# placa_servo2.net
KiCad netlist of a schematic drawn in EAGLE
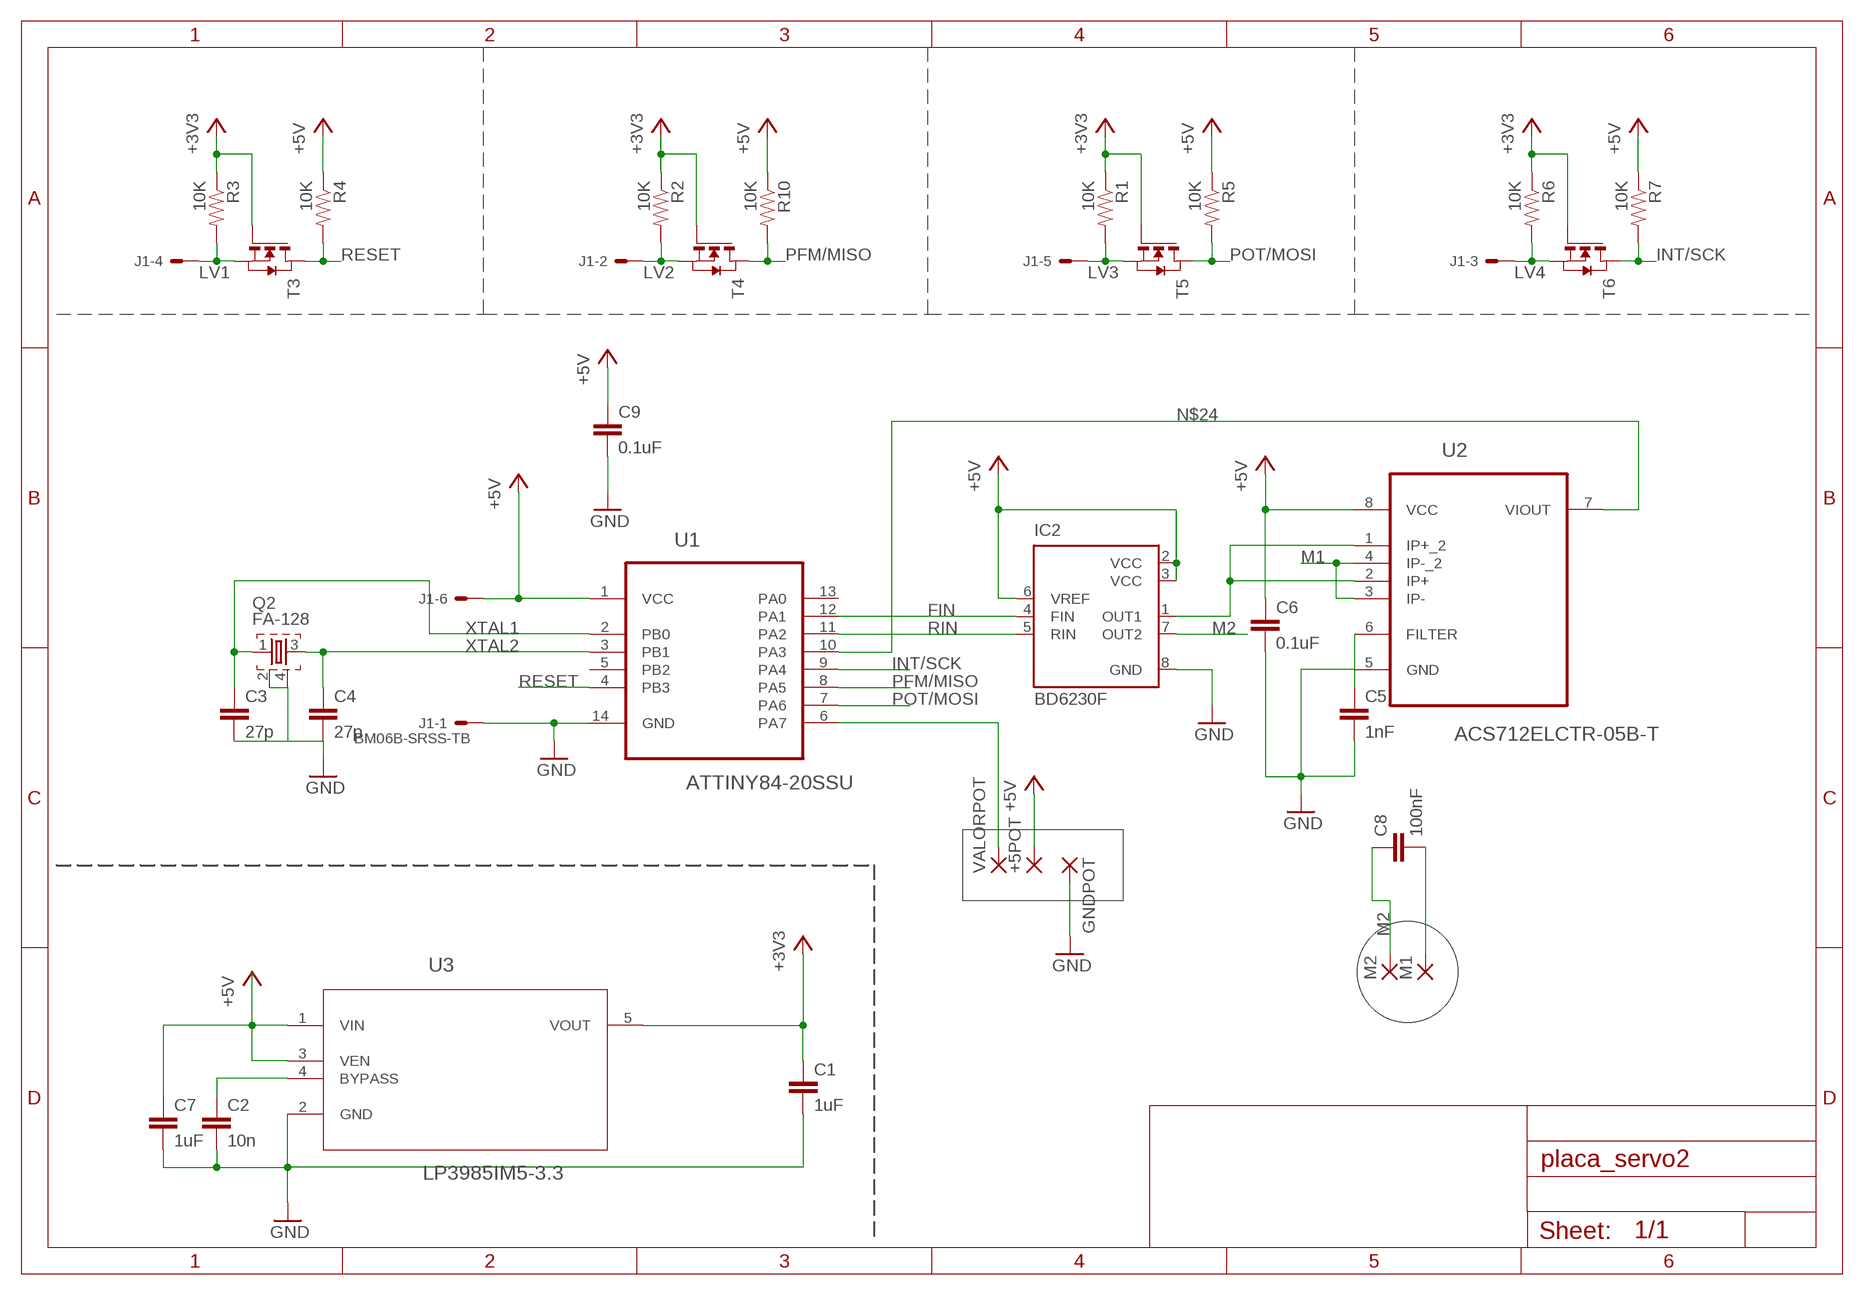
[diagram p0: schematic, sheet 1]

(export (version "E")
  (design (tool "Eeschema 10.0.6"))
  (components
    (comp (ref "+5POT")
      (value "1,6/0,9")
      (footprint "eagle-import:1,6_0,9")
      (libsource (lib "eagle-import") (part "1,6/0,9"))
    )
    (comp (ref "C1")
      (value "1uF")
      (footprint "eagle-import:C0603")
      (libsource (lib "eagle-import") (part "C-EUC0603"))
    )
    (comp (ref "C2")
      (value "10n")
      (footprint "eagle-import:C0603")
      (libsource (lib "eagle-import") (part "C-EUC0603"))
    )
    (comp (ref "C3")
      (value "27p")
      (footprint "eagle-import:C0603")
      (libsource (lib "eagle-import") (part "resistor_C-EUC0603"))
    )
    (comp (ref "C4")
      (value "27p")
      (footprint "eagle-import:C0603")
      (libsource (lib "eagle-import") (part "resistor_C-EUC0603"))
    )
    (comp (ref "C5")
      (value "1nF")
      (footprint "eagle-import:C0603")
      (libsource (lib "eagle-import") (part "C-EUC0603"))
    )
    (comp (ref "C6")
      (value "0.1uF")
      (footprint "eagle-import:C0603")
      (libsource (lib "eagle-import") (part "C-EUC0603"))
    )
    (comp (ref "C7")
      (value "1uF")
      (footprint "eagle-import:C0603")
      (libsource (lib "eagle-import") (part "C-EUC0603"))
    )
    (comp (ref "C8")
      (value "100nF")
      (footprint "eagle-import:C0603")
      (libsource (lib "eagle-import") (part "C-EUC0603"))
    )
    (comp (ref "C9")
      (value "0.1uF")
      (footprint "eagle-import:C0603")
      (libsource (lib "eagle-import") (part "C-EUC0603"))
    )
    (comp (ref "GNDPOT")
      (value "1,6/0,9")
      (footprint "eagle-import:1,6_0,9")
      (libsource (lib "eagle-import") (part "1,6/0,9"))
    )
    (comp (ref "IC2")
      (value "BD6230F")
      (footprint "eagle-import:SOP8")
      (fields (field (name "MPN") "BD6230F-E2"))
      (libsource (lib "eagle-import") (part "BD623F0"))
    )
    (comp (ref "J1")
      (value "BM06B-SRSS-TB")
      (footprint "eagle-import:BM06B-SRSS-TB")
      (libsource (lib "eagle-import") (part "?M06B-SRSS-TBB"))
    )
    (comp (ref "M1")
      (value "1,6/0,9")
      (footprint "eagle-import:1,6_0,9")
      (libsource (lib "eagle-import") (part "1,6/0,9"))
    )
    (comp (ref "M2")
      (value "1,6/0,9")
      (footprint "eagle-import:1,6_0,9")
      (libsource (lib "eagle-import") (part "1,6/0,9"))
    )
    (comp (ref "Q2")
      (value "FA-128")
      (footprint "eagle-import:FA-128")
      (libsource (lib "eagle-import") (part "FA-128"))
    )
    (comp (ref "R1")
      (value "10K")
      (footprint "eagle-import:0603-RES")
      (libsource (lib "eagle-import") (part "RESISTOR0603-RES"))
    )
    (comp (ref "R2")
      (value "10K")
      (footprint "eagle-import:0603-RES")
      (libsource (lib "eagle-import") (part "RESISTOR0603-RES"))
    )
    (comp (ref "R3")
      (value "10K")
      (footprint "eagle-import:0603-RES")
      (libsource (lib "eagle-import") (part "RESISTOR0603-RES"))
    )
    (comp (ref "R4")
      (value "10K")
      (footprint "eagle-import:0603-RES")
      (libsource (lib "eagle-import") (part "RESISTOR0603-RES"))
    )
    (comp (ref "R5")
      (value "10K")
      (footprint "eagle-import:0603-RES")
      (libsource (lib "eagle-import") (part "RESISTOR0603-RES"))
    )
    (comp (ref "R6")
      (value "10K")
      (footprint "eagle-import:0603-RES")
      (libsource (lib "eagle-import") (part "RESISTOR0603-RES"))
    )
    (comp (ref "R7")
      (value "10K")
      (footprint "eagle-import:0603-RES")
      (libsource (lib "eagle-import") (part "RESISTOR0603-RES"))
    )
    (comp (ref "R10")
      (value "10K")
      (footprint "eagle-import:0603-RES")
      (libsource (lib "eagle-import") (part "RESISTOR0603-RES"))
    )
    (comp (ref "T3")
      (value "NMOSSOT23")
      (footprint "eagle-import:SOT-23")
      (libsource (lib "eagle-import") (part "NMOSSOT23"))
    )
    (comp (ref "T4")
      (value "NMOSSOT23")
      (footprint "eagle-import:SOT-23")
      (libsource (lib "eagle-import") (part "NMOSSOT23"))
    )
    (comp (ref "T5")
      (value "NMOSSOT23")
      (footprint "eagle-import:SOT-23")
      (libsource (lib "eagle-import") (part "NMOSSOT23"))
    )
    (comp (ref "T6")
      (value "NMOSSOT23")
      (footprint "eagle-import:SOT-23")
      (libsource (lib "eagle-import") (part "NMOSSOT23"))
    )
    (comp (ref "U1")
      (value "ATTINY84-20SSU")
      (footprint "eagle-import:SOIC127P600X175-14N")
      (libsource (lib "eagle-import") (part "ATTINY84-20SSU"))
    )
    (comp (ref "U2")
      (value "ACS712ELCTR-05B-T")
      (footprint "eagle-import:SOIC127P600X175-8N")
      (libsource (lib "eagle-import") (part "ACS712ELCTR-05B-T"))
    )
    (comp (ref "U3")
      (value "LP3985IM5-3.3")
      (footprint "eagle-import:SOT95P300X120-5N")
      (libsource (lib "eagle-import") (part "LP3985IM5-3.3"))
    )
    (comp (ref "VALORPOT")
      (value "1,6/0,9")
      (footprint "eagle-import:1,6_0,9")
      (libsource (lib "eagle-import") (part "1,6/0,9"))
    )
  )
  (nets
    (net (code "1") (name "+3V3") (class "Default")
      (node (ref "C1") (pin "1") (pinfunction "1_1") (pintype "passive"))
      (node (ref "R1") (pin "1") (pinfunction "1_1") (pintype "passive"))
      (node (ref "R2") (pin "1") (pinfunction "1_1") (pintype "passive"))
      (node (ref "R3") (pin "1") (pinfunction "1_1") (pintype "passive"))
      (node (ref "R6") (pin "1") (pinfunction "1_1") (pintype "passive"))
      (node (ref "T3") (pin "3") (pinfunction "G_3") (pintype "passive"))
      (node (ref "T4") (pin "3") (pinfunction "G_3") (pintype "passive"))
      (node (ref "T5") (pin "3") (pinfunction "G_3") (pintype "passive"))
      (node (ref "T6") (pin "3") (pinfunction "G_3") (pintype "passive"))
      (node (ref "U3") (pin "5") (pinfunction "VOUT_5") (pintype "output"))
    )
    (net (code "2") (name "+5V") (class "Default")
      (node (ref "+5POT") (pin "1") (pinfunction "P_1") (pintype "passive"))
      (node (ref "C6") (pin "1") (pinfunction "1_1") (pintype "passive"))
      (node (ref "C7") (pin "1") (pinfunction "1_1") (pintype "passive"))
      (node (ref "C9") (pin "1") (pinfunction "1_1") (pintype "passive"))
      (node (ref "IC2") (pin "2") (pinfunction "VCC_2") (pintype "power_in"))
      (node (ref "IC2") (pin "3") (pinfunction "VCC_3") (pintype "power_in"))
      (node (ref "IC2") (pin "6") (pinfunction "VREF_6") (pintype "passive"))
      (node (ref "J1") (pin "6") (pinfunction "S_6") (pintype "passive"))
      (node (ref "R10") (pin "1") (pinfunction "1_1") (pintype "passive"))
      (node (ref "R4") (pin "1") (pinfunction "1_1") (pintype "passive"))
      (node (ref "R5") (pin "1") (pinfunction "1_1") (pintype "passive"))
      (node (ref "R7") (pin "1") (pinfunction "1_1") (pintype "passive"))
      (node (ref "U1") (pin "1") (pinfunction "VCC_1") (pintype "power_in"))
      (node (ref "U2") (pin "8") (pinfunction "VCC_8") (pintype "power_in"))
      (node (ref "U3") (pin "1") (pinfunction "VIN_1") (pintype "power_in"))
      (node (ref "U3") (pin "3") (pinfunction "VEN_3") (pintype "input"))
    )
    (net (code "3") (name "/FIN") (class "Default")
      (node (ref "IC2") (pin "4") (pinfunction "FIN_4") (pintype "input"))
      (node (ref "U1") (pin "12") (pinfunction "PA1_12") (pintype "bidirectional"))
    )
    (net (code "4") (name "/INT{slash}SCK") (class "Default")
      (node (ref "R7") (pin "2") (pinfunction "2_2") (pintype "passive"))
      (node (ref "T6") (pin "1") (pinfunction "D_1") (pintype "passive"))
      (node (ref "U1") (pin "9") (pinfunction "PA4_9") (pintype "bidirectional"))
    )
    (net (code "5") (name "/LV1") (class "Default")
      (node (ref "J1") (pin "4") (pinfunction "S_4") (pintype "passive"))
      (node (ref "R3") (pin "2") (pinfunction "2_2") (pintype "passive"))
      (node (ref "T3") (pin "2") (pinfunction "S_2") (pintype "passive"))
    )
    (net (code "6") (name "/LV2") (class "Default")
      (node (ref "J1") (pin "2") (pinfunction "S_2") (pintype "passive"))
      (node (ref "R2") (pin "2") (pinfunction "2_2") (pintype "passive"))
      (node (ref "T4") (pin "2") (pinfunction "S_2") (pintype "passive"))
    )
    (net (code "7") (name "/LV3") (class "Default")
      (node (ref "J1") (pin "5") (pinfunction "S_5") (pintype "passive"))
      (node (ref "R1") (pin "2") (pinfunction "2_2") (pintype "passive"))
      (node (ref "T5") (pin "2") (pinfunction "S_2") (pintype "passive"))
    )
    (net (code "8") (name "/LV4") (class "Default")
      (node (ref "J1") (pin "3") (pinfunction "S_3") (pintype "passive"))
      (node (ref "R6") (pin "2") (pinfunction "2_2") (pintype "passive"))
      (node (ref "T6") (pin "2") (pinfunction "S_2") (pintype "passive"))
    )
    (net (code "9") (name "/M1") (class "Default")
      (node (ref "C8") (pin "2") (pinfunction "2_2") (pintype "passive"))
      (node (ref "M1") (pin "1") (pinfunction "P_1") (pintype "passive"))
      (node (ref "U2") (pin "3") (pinfunction "IP-_3") (pintype "input"))
      (node (ref "U2") (pin "4") (pinfunction "IP-_2_4") (pintype "input"))
    )
    (net (code "10") (name "/M2") (class "Default")
      (node (ref "C8") (pin "1") (pinfunction "1_1") (pintype "passive"))
      (node (ref "IC2") (pin "7") (pinfunction "OUT2_7") (pintype "output"))
      (node (ref "M2") (pin "1") (pinfunction "P_1") (pintype "passive"))
    )
    (net (code "11") (name "/N$24") (class "Default")
      (node (ref "U1") (pin "10") (pinfunction "PA3_10") (pintype "bidirectional"))
      (node (ref "U2") (pin "7") (pinfunction "VIOUT_7") (pintype "output"))
    )
    (net (code "12") (name "/PFM{slash}MISO") (class "Default")
      (node (ref "R10") (pin "2") (pinfunction "2_2") (pintype "passive"))
      (node (ref "T4") (pin "1") (pinfunction "D_1") (pintype "passive"))
      (node (ref "U1") (pin "8") (pinfunction "PA5_8") (pintype "bidirectional"))
    )
    (net (code "13") (name "/POT{slash}MOSI") (class "Default")
      (node (ref "R5") (pin "2") (pinfunction "2_2") (pintype "passive"))
      (node (ref "T5") (pin "1") (pinfunction "D_1") (pintype "passive"))
      (node (ref "U1") (pin "7") (pinfunction "PA6_7") (pintype "bidirectional"))
    )
    (net (code "14") (name "/RESET") (class "Default")
      (node (ref "R4") (pin "2") (pinfunction "2_2") (pintype "passive"))
      (node (ref "T3") (pin "1") (pinfunction "D_1") (pintype "passive"))
      (node (ref "U1") (pin "4") (pinfunction "PB3_4") (pintype "bidirectional"))
    )
    (net (code "15") (name "/RIN") (class "Default")
      (node (ref "IC2") (pin "5") (pinfunction "RIN_5") (pintype "input"))
      (node (ref "U1") (pin "11") (pinfunction "PA2_11") (pintype "bidirectional"))
    )
    (net (code "16") (name "/XTAL1") (class "Default")
      (node (ref "C3") (pin "1") (pinfunction "1_1") (pintype "passive"))
      (node (ref "Q2") (pin "1") (pinfunction "1_1") (pintype "passive"))
      (node (ref "U1") (pin "2") (pinfunction "PB0_2") (pintype "bidirectional"))
    )
    (net (code "17") (name "/XTAL2") (class "Default")
      (node (ref "C4") (pin "1") (pinfunction "1_1") (pintype "passive"))
      (node (ref "Q2") (pin "3") (pinfunction "3_3") (pintype "passive"))
      (node (ref "U1") (pin "3") (pinfunction "PB1_3") (pintype "bidirectional"))
    )
    (net (code "18") (name "GND") (class "Default")
      (node (ref "C1") (pin "2") (pinfunction "2_2") (pintype "passive"))
      (node (ref "C2") (pin "2") (pinfunction "2_2") (pintype "passive"))
      (node (ref "C3") (pin "2") (pinfunction "2_2") (pintype "passive"))
      (node (ref "C4") (pin "2") (pinfunction "2_2") (pintype "passive"))
      (node (ref "C5") (pin "2") (pinfunction "2_2") (pintype "passive"))
      (node (ref "C6") (pin "2") (pinfunction "2_2") (pintype "passive"))
      (node (ref "C7") (pin "2") (pinfunction "2_2") (pintype "passive"))
      (node (ref "C9") (pin "2") (pinfunction "2_2") (pintype "passive"))
      (node (ref "GNDPOT") (pin "1") (pinfunction "P_1") (pintype "passive"))
      (node (ref "IC2") (pin "8") (pinfunction "GND_8") (pintype "power_in"))
      (node (ref "J1") (pin "1") (pinfunction "S_1") (pintype "passive"))
      (node (ref "Q2") (pin "2") (pinfunction "2_2") (pintype "passive"))
      (node (ref "Q2") (pin "4") (pinfunction "4_4") (pintype "passive"))
      (node (ref "U1") (pin "14") (pinfunction "GND_14") (pintype "passive"))
      (node (ref "U2") (pin "5") (pinfunction "GND_5") (pintype "passive"))
      (node (ref "U3") (pin "2") (pinfunction "GND_2") (pintype "passive"))
    )
    (net (code "19") (name "Net-(IC2-OUT1)") (class "Default")
      (node (ref "IC2") (pin "1") (pinfunction "OUT1_1") (pintype "output"))
      (node (ref "U2") (pin "1") (pinfunction "IP+_2_1") (pintype "input"))
      (node (ref "U2") (pin "2") (pinfunction "IP+_2") (pintype "input"))
    )
    (net (code "20") (name "Net-(U1-PA7)") (class "Default")
      (node (ref "U1") (pin "6") (pinfunction "PA7_6") (pintype "bidirectional"))
      (node (ref "VALORPOT") (pin "1") (pinfunction "P_1") (pintype "passive"))
    )
    (net (code "21") (name "Net-(U2-FILTER)") (class "Default")
      (node (ref "C5") (pin "1") (pinfunction "1_1") (pintype "passive"))
      (node (ref "U2") (pin "6") (pinfunction "FILTER_6") (pintype "input"))
    )
    (net (code "22") (name "Net-(U3-BYPASS)") (class "Default")
      (node (ref "C2") (pin "1") (pinfunction "1_1") (pintype "passive"))
      (node (ref "U3") (pin "4") (pinfunction "BYPASS_4") (pintype "input"))
    )
    (net (code "23") (name "unconnected-(U1-PA0-Pad13)") (class "Default")
      (node (ref "U1") (pin "13") (pinfunction "PA0_13") (pintype "bidirectional"))
    )
    (net (code "24") (name "unconnected-(U1-PB2-Pad5)") (class "Default")
      (node (ref "U1") (pin "5") (pinfunction "PB2_5") (pintype "bidirectional"))
    )
  )
)
